# USB.net
KiCad netlist of a schematic drawn in Altium Designer
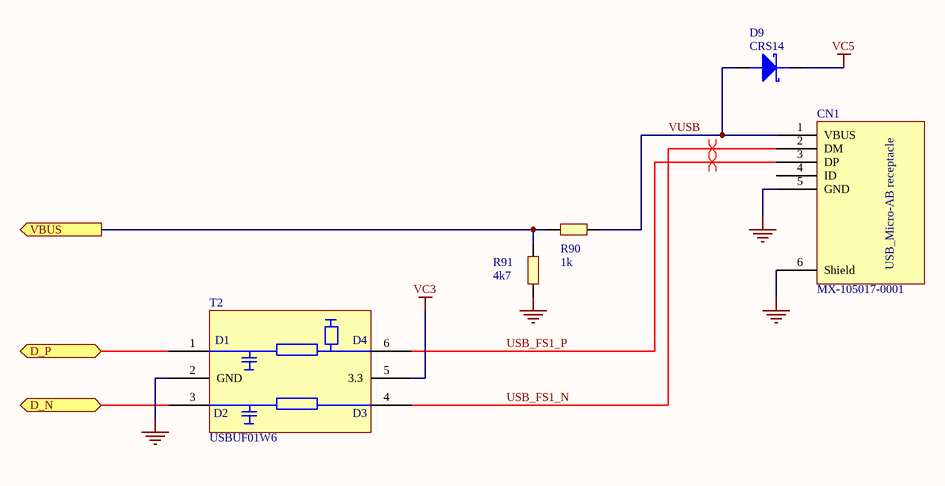
[diagram p0: USB.SchDoc]

(export (version "E")
  (design (tool "Eeschema 10.0.6"))
  (components
    (comp (ref "CN1")
      (value "MX-105017-0001")
      (footprint "MOLEX_MICROUSB_MX-105017-0001")
      (description "USB-MICRO-AB, 47590-0001, SMT, MOLEX")
      (libsource (lib "MCD_TOOLS") (part "USB-MICRO-AB"))
    )
    (comp (ref "D9")
      (value "CRS14")
      (footprint "1206D")
      (description "Schottky Diode")
      (libsource (lib "*") (part "DIODE SCHOTTKY"))
    )
    (comp (ref "R90") (value "1k") (footprint "0805R") (libsource (lib "*") (part "RES3")))
    (comp (ref "R91") (value "4k7") (footprint "0805R") (libsource (lib "") (part "RES3_1")))
    (comp (ref "T2") (value "USBUF01W6") (footprint "SOTT323-6L") (libsource (lib "*") (part "USBUF01W6")))
  )
  (nets
    (net (code "1") (name "/D_N") (class "Default")
      (node (ref "T2") (pin "3") (pinfunction "D2_3") (pintype "passive"))
    )
    (net (code "2") (name "/D_P") (class "Default")
      (node (ref "T2") (pin "1") (pinfunction "D1_1") (pintype "passive"))
    )
    (net (code "3") (name "/USB_FS1_N") (class "Default")
      (node (ref "CN1") (pin "2") (pinfunction "DM_2") (pintype "passive"))
      (node (ref "T2") (pin "4") (pinfunction "D3_4") (pintype "passive"))
    )
    (net (code "4") (name "/USB_FS1_P") (class "Default")
      (node (ref "CN1") (pin "3") (pinfunction "DP_3") (pintype "passive"))
      (node (ref "T2") (pin "6") (pinfunction "D4_6") (pintype "passive"))
    )
    (net (code "5") (name "/VBUS") (class "Default")
      (node (ref "R90") (pin "2") (pintype "passive"))
      (node (ref "R91") (pin "1") (pintype "passive"))
    )
    (net (code "6") (name "/VUSB") (class "Default")
      (node (ref "CN1") (pin "1") (pinfunction "VBUS_1") (pintype "passive"))
      (node (ref "D9") (pin "A") (pinfunction "A_A") (pintype "passive"))
      (node (ref "R90") (pin "1") (pintype "passive"))
    )
    (net (code "7") (name "GND") (class "Default")
      (node (ref "CN1") (pin "5") (pinfunction "GND_5") (pintype "passive"))
      (node (ref "CN1") (pin "6") (pinfunction "Shield_6") (pintype "passive"))
      (node (ref "R91") (pin "2") (pintype "passive"))
      (node (ref "T2") (pin "2") (pinfunction "GND_2") (pintype "passive"))
    )
    (net (code "8") (name "VC3") (class "Default")
      (node (ref "T2") (pin "5") (pinfunction "3.3_5") (pintype "passive"))
    )
    (net (code "9") (name "VC5") (class "Default")
      (node (ref "D9") (pin "K") (pinfunction "K_K") (pintype "passive"))
    )
    (net (code "10") (name "unconnected-(CN1-ID-Pad4)") (class "Default")
      (node (ref "CN1") (pin "4") (pinfunction "ID_4") (pintype "passive"))
    )
  )
)
